# Sheet3.net
KiCad netlist of a schematic drawn in Altium Designer
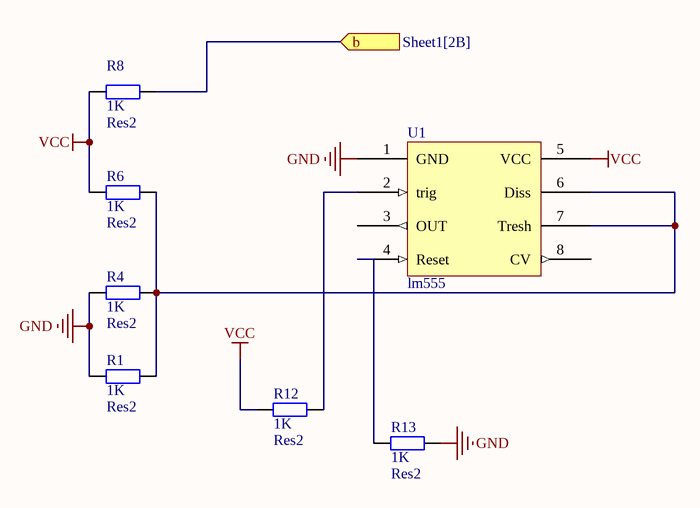
[diagram p0: Sheet3.SchDoc]

(export (version "E")
  (design (tool "Eeschema 10.0.6"))
  (components
    (comp (ref "R1")
      (value "Res2")
      (footprint "AXIAL-0.4")
      (description "Resistor")
      (fields (field (name "ALTIUM_VALUE") "1K") (field (name "PUBLISHER") "Altium Limited"))
      (libsource (lib "Miscellaneous Devices") (part "Res2"))
    )
    (comp (ref "R4")
      (value "Res2")
      (footprint "AXIAL-0.4")
      (description "Resistor")
      (fields (field (name "ALTIUM_VALUE") "1K") (field (name "PUBLISHER") "Altium Limited"))
      (libsource (lib "Miscellaneous Devices") (part "Res2"))
    )
    (comp (ref "R6")
      (value "Res2")
      (footprint "AXIAL-0.4")
      (description "Resistor")
      (fields (field (name "ALTIUM_VALUE") "1K") (field (name "PUBLISHER") "Altium Limited"))
      (libsource (lib "Miscellaneous Devices") (part "Res2"))
    )
    (comp (ref "R8")
      (value "Res2")
      (footprint "AXIAL-0.4")
      (description "Resistor")
      (fields (field (name "ALTIUM_VALUE") "1K") (field (name "PUBLISHER") "Altium Limited"))
      (libsource (lib "Miscellaneous Devices") (part "Res2"))
    )
    (comp (ref "R12")
      (value "Res2")
      (footprint "AXIAL-0.4")
      (description "Resistor")
      (fields (field (name "ALTIUM_VALUE") "1K") (field (name "PUBLISHER") "Altium Limited"))
      (libsource (lib "Miscellaneous Devices") (part "Res2"))
    )
    (comp (ref "R13")
      (value "Res2")
      (footprint "AXIAL-0.4")
      (description "Resistor")
      (fields (field (name "ALTIUM_VALUE") "1K") (field (name "PUBLISHER") "Altium Limited"))
      (libsource (lib "Miscellaneous Devices") (part "Res2"))
    )
    (comp (ref "U1") (value "lm555") (footprint "DIP8") (libsource (lib "Schlib1") (part "lm555")))
  )
  (nets
    (net (code "1") (name "/b") (class "Default")
      (node (ref "R8") (pin "2") (pinfunction "2_2") (pintype "passive"))
    )
    (net (code "2") (name "GND") (class "Default")
      (node (ref "R1") (pin "1") (pinfunction "1_1") (pintype "passive"))
      (node (ref "R13") (pin "2") (pinfunction "2_2") (pintype "passive"))
      (node (ref "R4") (pin "1") (pinfunction "1_1") (pintype "passive"))
      (node (ref "U1") (pin "1") (pinfunction "GND_1") (pintype "power_in"))
    )
    (net (code "3") (name "Net-(U1-Diss)") (class "Default")
      (node (ref "R1") (pin "2") (pinfunction "2_2") (pintype "passive"))
      (node (ref "R4") (pin "2") (pinfunction "2_2") (pintype "passive"))
      (node (ref "R6") (pin "2") (pinfunction "2_2") (pintype "passive"))
      (node (ref "U1") (pin "6") (pinfunction "Diss_6") (pintype "passive"))
      (node (ref "U1") (pin "7") (pinfunction "Tresh_7") (pintype "passive"))
    )
    (net (code "4") (name "Net-(U1-Reset)") (class "Default")
      (node (ref "R13") (pin "1") (pinfunction "1_1") (pintype "passive"))
      (node (ref "U1") (pin "4") (pinfunction "Reset_4") (pintype "input"))
    )
    (net (code "5") (name "Net-(U1-trig)") (class "Default")
      (node (ref "R12") (pin "2") (pinfunction "2_2") (pintype "passive"))
      (node (ref "U1") (pin "2") (pinfunction "trig_2") (pintype "input"))
    )
    (net (code "6") (name "VCC") (class "Default")
      (node (ref "R12") (pin "1") (pinfunction "1_1") (pintype "passive"))
      (node (ref "R6") (pin "1") (pinfunction "1_1") (pintype "passive"))
      (node (ref "R8") (pin "1") (pinfunction "1_1") (pintype "passive"))
      (node (ref "U1") (pin "5") (pinfunction "VCC_5") (pintype "power_in"))
    )
    (net (code "7") (name "unconnected-(U1-CV-Pad8)") (class "Default")
      (node (ref "U1") (pin "8") (pinfunction "CV_8") (pintype "output"))
    )
    (net (code "8") (name "unconnected-(U1-OUT-Pad3)") (class "Default")
      (node (ref "U1") (pin "3") (pinfunction "OUT_3") (pintype "output"))
    )
  )
)
